# ads1299.net
KiCad netlist of a schematic drawn in Altium Designer
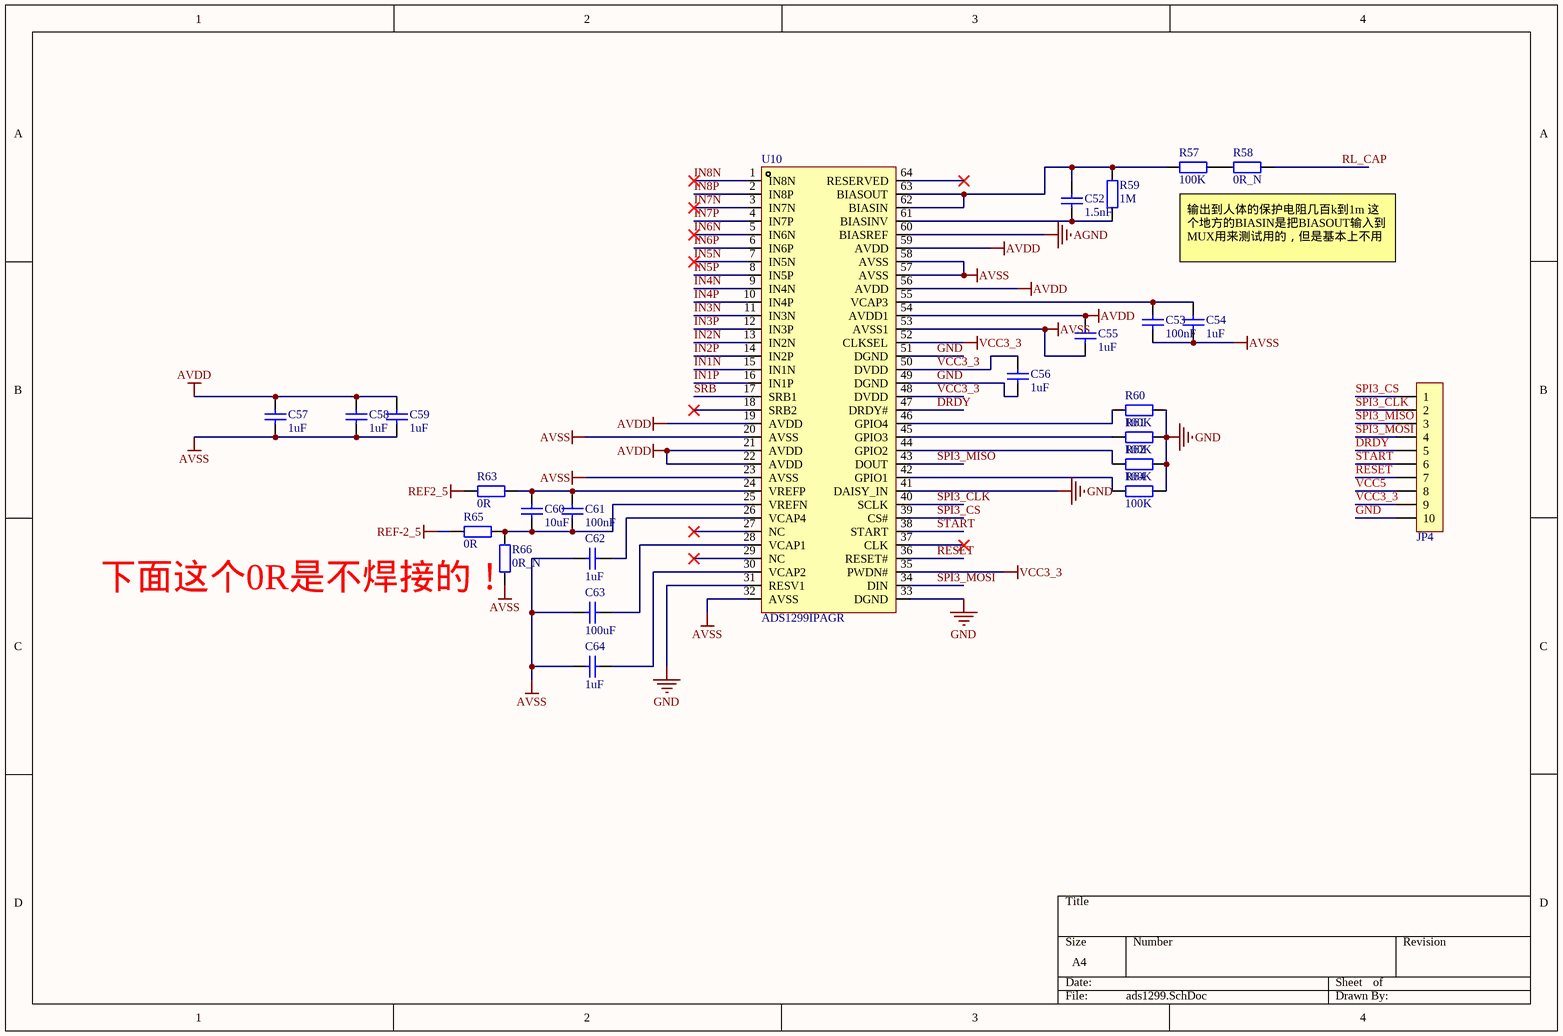
[diagram p0: ads1299.SchDoc]

(export (version "E")
  (design (tool "Eeschema 10.0.6"))
  (components
    (comp (ref "C52")
      (value "1.5nF")
      (footprint "C0603_L")
      (description "贴片电容/MLCC电容")
      (libsource (lib "0.1 - 电阻-电容-电感-保险丝-晶振-晶体-磁珠-电位器-法拉电容-馈通电容") (part "C"))
    )
    (comp (ref "C53")
      (value "100nF")
      (footprint "C0603_L")
      (description "贴片电容/MLCC电容")
      (libsource (lib "0.1 - 电阻-电容-电感-保险丝-晶振-晶体-磁珠-电位器-法拉电容-馈通电容") (part "C"))
    )
    (comp (ref "C54")
      (value "1uF")
      (footprint "C0603_L")
      (description "贴片电容/MLCC电容")
      (libsource (lib "0.1 - 电阻-电容-电感-保险丝-晶振-晶体-磁珠-电位器-法拉电容-馈通电容") (part "C"))
    )
    (comp (ref "C55")
      (value "1uF")
      (footprint "C0603_L")
      (description "贴片电容/MLCC电容")
      (libsource (lib "0.1 - 电阻-电容-电感-保险丝-晶振-晶体-磁珠-电位器-法拉电容-馈通电容") (part "C"))
    )
    (comp (ref "C56")
      (value "1uF")
      (footprint "C0603_L")
      (description "贴片电容/MLCC电容")
      (libsource (lib "0.1 - 电阻-电容-电感-保险丝-晶振-晶体-磁珠-电位器-法拉电容-馈通电容") (part "C"))
    )
    (comp (ref "C57")
      (value "1uF")
      (footprint "C0603_L")
      (description "贴片电容/MLCC电容")
      (libsource (lib "0.1 - 电阻-电容-电感-保险丝-晶振-晶体-磁珠-电位器-法拉电容-馈通电容") (part "C"))
    )
    (comp (ref "C58")
      (value "1uF")
      (footprint "C0603_L")
      (description "贴片电容/MLCC电容")
      (libsource (lib "0.1 - 电阻-电容-电感-保险丝-晶振-晶体-磁珠-电位器-法拉电容-馈通电容") (part "C"))
    )
    (comp (ref "C59")
      (value "1uF")
      (footprint "C0603_L")
      (description "贴片电容/MLCC电容")
      (libsource (lib "0.1 - 电阻-电容-电感-保险丝-晶振-晶体-磁珠-电位器-法拉电容-馈通电容") (part "C"))
    )
    (comp (ref "C60")
      (value "10uF")
      (footprint "C0603_L")
      (description "贴片电容/MLCC电容")
      (libsource (lib "0.1 - 电阻-电容-电感-保险丝-晶振-晶体-磁珠-电位器-法拉电容-馈通电容") (part "C"))
    )
    (comp (ref "C61")
      (value "100nF")
      (footprint "C0603_L")
      (description "贴片电容/MLCC电容")
      (libsource (lib "0.1 - 电阻-电容-电感-保险丝-晶振-晶体-磁珠-电位器-法拉电容-馈通电容") (part "C"))
    )
    (comp (ref "C62")
      (value "1uF")
      (footprint "C0603_L")
      (description "贴片电容/MLCC电容")
      (libsource (lib "0.1 - 电阻-电容-电感-保险丝-晶振-晶体-磁珠-电位器-法拉电容-馈通电容") (part "C"))
    )
    (comp (ref "C63")
      (value "100uF")
      (footprint "C1206_L")
      (description "贴片电容/MLCC电容")
      (libsource (lib "0.1 - 电阻-电容-电感-保险丝-晶振-晶体-磁珠-电位器-法拉电容-馈通电容") (part "C"))
    )
    (comp (ref "C64")
      (value "1uF")
      (footprint "C0603_L")
      (description "贴片电容/MLCC电容")
      (libsource (lib "0.1 - 电阻-电容-电感-保险丝-晶振-晶体-磁珠-电位器-法拉电容-馈通电容") (part "C"))
    )
    (comp (ref "JP4")
      (value "HDR-1X10")
      (footprint "HDR2.54-LI-10P")
      (description "10P接插件")
      (libsource (lib "5.5 - 2.54mm连接器(KF2EDGK_XH2.54_2.54排针排母)") (part "Header 10"))
    )
    (comp (ref "R57")
      (value "100K")
      (footprint "R0603_L")
      (description "贴片电阻")
      (libsource (lib "0.1 - 电阻-电容-电感-保险丝-晶振-晶体-磁珠-电位器-法拉电容-馈通电容") (part "R"))
    )
    (comp (ref "R58")
      (value "0R_N")
      (footprint "R0603_L")
      (description "贴片电阻")
      (libsource (lib "0.1 - 电阻-电容-电感-保险丝-晶振-晶体-磁珠-电位器-法拉电容-馈通电容") (part "R"))
    )
    (comp (ref "R59")
      (value "1M")
      (footprint "R0603_L")
      (description "贴片电阻")
      (libsource (lib "0.1 - 电阻-电容-电感-保险丝-晶振-晶体-磁珠-电位器-法拉电容-馈通电容") (part "R"))
    )
    (comp (ref "R60")
      (value "100K")
      (footprint "R0603_L")
      (description "贴片电阻")
      (libsource (lib "0.1 - 电阻-电容-电感-保险丝-晶振-晶体-磁珠-电位器-法拉电容-馈通电容") (part "R"))
    )
    (comp (ref "R61")
      (value "100K")
      (footprint "R0603_L")
      (description "贴片电阻")
      (libsource (lib "0.1 - 电阻-电容-电感-保险丝-晶振-晶体-磁珠-电位器-法拉电容-馈通电容") (part "R"))
    )
    (comp (ref "R62")
      (value "100K")
      (footprint "R0603_L")
      (description "贴片电阻")
      (libsource (lib "0.1 - 电阻-电容-电感-保险丝-晶振-晶体-磁珠-电位器-法拉电容-馈通电容") (part "R"))
    )
    (comp (ref "R63")
      (value "0R")
      (footprint "R0603_L")
      (description "贴片电阻")
      (libsource (lib "0.1 - 电阻-电容-电感-保险丝-晶振-晶体-磁珠-电位器-法拉电容-馈通电容") (part "R"))
    )
    (comp (ref "R64")
      (value "100K")
      (footprint "R0603_L")
      (description "贴片电阻")
      (libsource (lib "0.1 - 电阻-电容-电感-保险丝-晶振-晶体-磁珠-电位器-法拉电容-馈通电容") (part "R"))
    )
    (comp (ref "R65")
      (value "0R")
      (footprint "R0603_L")
      (description "贴片电阻")
      (libsource (lib "0.1 - 电阻-电容-电感-保险丝-晶振-晶体-磁珠-电位器-法拉电容-馈通电容") (part "R"))
    )
    (comp (ref "R66")
      (value "0R_N")
      (footprint "R0603_L")
      (description "贴片电阻")
      (libsource (lib "0.1 - 电阻-电容-电感-保险丝-晶振-晶体-磁珠-电位器-法拉电容-馈通电容") (part "R"))
    )
    (comp (ref "U10")
      (value "ADS1299IPAGR")
      (footprint "TQFP64_N")
      (description "24位、多通道EEG/ECG ADC，内置增益放大")
      (fields (field (name "MANUFACTURER") "TI(德州仪器)"))
      (libsource (lib "HT") (part "ADS1299IPAGR"))
    )
  )
  (nets
    (net (code "1") (name "/DRDY") (class "Default")
      (node (ref "JP4") (pin "5") (pinfunction "5_5") (pintype "passive"))
      (node (ref "U10") (pin "47") (pinfunction "DRDY#_47") (pintype "passive"))
    )
    (net (code "2") (name "/IN1N") (class "Default")
      (node (ref "U10") (pin "15") (pinfunction "IN1N_15") (pintype "passive"))
    )
    (net (code "3") (name "/IN1P") (class "Default")
      (node (ref "U10") (pin "16") (pinfunction "IN1P_16") (pintype "passive"))
    )
    (net (code "4") (name "/IN2N") (class "Default")
      (node (ref "U10") (pin "13") (pinfunction "IN2N_13") (pintype "passive"))
    )
    (net (code "5") (name "/IN2P") (class "Default")
      (node (ref "U10") (pin "14") (pinfunction "IN2P_14") (pintype "passive"))
    )
    (net (code "6") (name "/IN3N") (class "Default")
      (node (ref "U10") (pin "11") (pinfunction "IN3N_11") (pintype "passive"))
    )
    (net (code "7") (name "/IN3P") (class "Default")
      (node (ref "U10") (pin "12") (pinfunction "IN3P_12") (pintype "passive"))
    )
    (net (code "8") (name "/IN4N") (class "Default")
      (node (ref "U10") (pin "9") (pinfunction "IN4N_9") (pintype "passive"))
    )
    (net (code "9") (name "/IN4P") (class "Default")
      (node (ref "U10") (pin "10") (pinfunction "IN4P_10") (pintype "passive"))
    )
    (net (code "10") (name "/IN5N") (class "Default")
      (node (ref "U10") (pin "7") (pinfunction "IN5N_7") (pintype "passive+no_connect"))
    )
    (net (code "11") (name "/IN5P") (class "Default")
      (node (ref "U10") (pin "8") (pinfunction "IN5P_8") (pintype "passive"))
    )
    (net (code "12") (name "/IN6N") (class "Default")
      (node (ref "U10") (pin "5") (pinfunction "IN6N_5") (pintype "passive+no_connect"))
    )
    (net (code "13") (name "/IN6P") (class "Default")
      (node (ref "U10") (pin "6") (pinfunction "IN6P_6") (pintype "passive"))
    )
    (net (code "14") (name "/IN7N") (class "Default")
      (node (ref "U10") (pin "3") (pinfunction "IN7N_3") (pintype "passive+no_connect"))
    )
    (net (code "15") (name "/IN7P") (class "Default")
      (node (ref "U10") (pin "4") (pinfunction "IN7P_4") (pintype "passive"))
    )
    (net (code "16") (name "/IN8N") (class "Default")
      (node (ref "U10") (pin "1") (pinfunction "IN8N_1") (pintype "passive+no_connect"))
    )
    (net (code "17") (name "/IN8P") (class "Default")
      (node (ref "U10") (pin "2") (pinfunction "IN8P_2") (pintype "passive"))
    )
    (net (code "18") (name "/RESET") (class "Default")
      (node (ref "JP4") (pin "7") (pinfunction "7_7") (pintype "passive"))
      (node (ref "U10") (pin "36") (pinfunction "RESET#_36") (pintype "passive"))
    )
    (net (code "19") (name "/RL_CAP") (class "Default")
      (node (ref "R58") (pin "1") (pinfunction "1_1") (pintype "passive"))
    )
    (net (code "20") (name "/SPI3_CLK") (class "Default")
      (node (ref "JP4") (pin "2") (pinfunction "2_2") (pintype "passive"))
      (node (ref "U10") (pin "40") (pinfunction "SCLK_40") (pintype "passive"))
    )
    (net (code "21") (name "/SPI3_CS") (class "Default")
      (node (ref "JP4") (pin "1") (pinfunction "1_1") (pintype "passive"))
      (node (ref "U10") (pin "39") (pinfunction "CS#_39") (pintype "passive"))
    )
    (net (code "22") (name "/SPI3_MISO") (class "Default")
      (node (ref "JP4") (pin "3") (pinfunction "3_3") (pintype "passive"))
      (node (ref "U10") (pin "43") (pinfunction "DOUT_43") (pintype "passive"))
    )
    (net (code "23") (name "/SPI3_MOSI") (class "Default")
      (node (ref "JP4") (pin "4") (pinfunction "4_4") (pintype "passive"))
      (node (ref "U10") (pin "34") (pinfunction "DIN_34") (pintype "passive"))
    )
    (net (code "24") (name "/SRB") (class "Default")
      (node (ref "U10") (pin "17") (pinfunction "SRB1_17") (pintype "passive"))
    )
    (net (code "25") (name "/START") (class "Default")
      (node (ref "JP4") (pin "6") (pinfunction "6_6") (pintype "passive"))
      (node (ref "U10") (pin "38") (pinfunction "START_38") (pintype "passive"))
    )
    (net (code "26") (name "/VCC5") (class "Default")
      (node (ref "JP4") (pin "8") (pinfunction "8_8") (pintype "passive"))
    )
    (net (code "27") (name "AGND") (class "Default")
      (node (ref "U10") (pin "60") (pinfunction "BIASREF_60") (pintype "passive"))
    )
    (net (code "28") (name "AVDD") (class "Default")
      (node (ref "C55") (pin "2") (pinfunction "2_2") (pintype "passive"))
      (node (ref "C57") (pin "2") (pinfunction "2_2") (pintype "passive"))
      (node (ref "C58") (pin "2") (pinfunction "2_2") (pintype "passive"))
      (node (ref "C59") (pin "2") (pinfunction "2_2") (pintype "passive"))
      (node (ref "U10") (pin "19") (pinfunction "AVDD_19") (pintype "passive"))
      (node (ref "U10") (pin "21") (pinfunction "AVDD_21") (pintype "passive"))
      (node (ref "U10") (pin "22") (pinfunction "AVDD_22") (pintype "passive"))
      (node (ref "U10") (pin "54") (pinfunction "AVDD1_54") (pintype "passive"))
      (node (ref "U10") (pin "56") (pinfunction "AVDD_56") (pintype "passive"))
      (node (ref "U10") (pin "59") (pinfunction "AVDD_59") (pintype "passive"))
    )
    (net (code "29") (name "AVSS") (class "Default")
      (node (ref "C53") (pin "1") (pinfunction "1_1") (pintype "passive"))
      (node (ref "C54") (pin "1") (pinfunction "1_1") (pintype "passive"))
      (node (ref "C55") (pin "1") (pinfunction "1_1") (pintype "passive"))
      (node (ref "C57") (pin "1") (pinfunction "1_1") (pintype "passive"))
      (node (ref "C58") (pin "1") (pinfunction "1_1") (pintype "passive"))
      (node (ref "C59") (pin "1") (pinfunction "1_1") (pintype "passive"))
      (node (ref "C62") (pin "1") (pinfunction "1_1") (pintype "passive"))
      (node (ref "C63") (pin "2") (pinfunction "2_2") (pintype "passive"))
      (node (ref "C64") (pin "1") (pinfunction "1_1") (pintype "passive"))
      (node (ref "R66") (pin "2") (pinfunction "2_2") (pintype "passive"))
      (node (ref "U10") (pin "20") (pinfunction "AVSS_20") (pintype "passive"))
      (node (ref "U10") (pin "23") (pinfunction "AVSS_23") (pintype "passive"))
      (node (ref "U10") (pin "32") (pinfunction "AVSS_32") (pintype "passive"))
      (node (ref "U10") (pin "53") (pinfunction "AVSS1_53") (pintype "passive"))
      (node (ref "U10") (pin "57") (pinfunction "AVSS_57") (pintype "passive"))
      (node (ref "U10") (pin "58") (pinfunction "AVSS_58") (pintype "passive"))
    )
    (net (code "30") (name "GND") (class "Default")
      (node (ref "C56") (pin "1") (pinfunction "1_1") (pintype "passive"))
      (node (ref "JP4") (pin "10") (pinfunction "10_10") (pintype "passive"))
      (node (ref "R60") (pin "2") (pinfunction "2_2") (pintype "passive"))
      (node (ref "R61") (pin "2") (pinfunction "2_2") (pintype "passive"))
      (node (ref "R62") (pin "2") (pinfunction "2_2") (pintype "passive"))
      (node (ref "R64") (pin "2") (pinfunction "2_2") (pintype "passive"))
      (node (ref "U10") (pin "31") (pinfunction "RESV1_31") (pintype "passive"))
      (node (ref "U10") (pin "33") (pinfunction "DGND_33") (pintype "passive"))
      (node (ref "U10") (pin "41") (pinfunction "DAISY_IN_41") (pintype "passive"))
      (node (ref "U10") (pin "49") (pinfunction "DGND_49") (pintype "passive"))
      (node (ref "U10") (pin "51") (pinfunction "DGND_51") (pintype "passive"))
    )
    (net (code "31") (name "Net-(R57-Pad2)") (class "Default")
      (node (ref "R57") (pin "2") (pinfunction "2_2") (pintype "passive"))
      (node (ref "R58") (pin "2") (pinfunction "2_2") (pintype "passive"))
    )
    (net (code "32") (name "Net-(U10-BIASIN)") (class "Default")
      (node (ref "C52") (pin "2") (pinfunction "2_2") (pintype "passive"))
      (node (ref "R57") (pin "1") (pinfunction "1_1") (pintype "passive"))
      (node (ref "R59") (pin "1") (pinfunction "1_1") (pintype "passive"))
      (node (ref "U10") (pin "62") (pinfunction "BIASIN_62") (pintype "passive"))
      (node (ref "U10") (pin "63") (pinfunction "BIASOUT_63") (pintype "passive"))
    )
    (net (code "33") (name "Net-(U10-BIASINV)") (class "Default")
      (node (ref "C52") (pin "1") (pinfunction "1_1") (pintype "passive"))
      (node (ref "R59") (pin "2") (pinfunction "2_2") (pintype "passive"))
      (node (ref "U10") (pin "61") (pinfunction "BIASINV_61") (pintype "passive"))
    )
    (net (code "34") (name "Net-(U10-GPIO1)") (class "Default")
      (node (ref "R64") (pin "1") (pinfunction "1_1") (pintype "passive"))
      (node (ref "U10") (pin "42") (pinfunction "GPIO1_42") (pintype "passive"))
    )
    (net (code "35") (name "Net-(U10-GPIO2)") (class "Default")
      (node (ref "R62") (pin "1") (pinfunction "1_1") (pintype "passive"))
      (node (ref "U10") (pin "44") (pinfunction "GPIO2_44") (pintype "passive"))
    )
    (net (code "36") (name "Net-(U10-GPIO3)") (class "Default")
      (node (ref "R61") (pin "1") (pinfunction "1_1") (pintype "passive"))
      (node (ref "U10") (pin "45") (pinfunction "GPIO3_45") (pintype "passive"))
    )
    (net (code "37") (name "Net-(U10-GPIO4)") (class "Default")
      (node (ref "R60") (pin "1") (pinfunction "1_1") (pintype "passive"))
      (node (ref "U10") (pin "46") (pinfunction "GPIO4_46") (pintype "passive"))
    )
    (net (code "38") (name "Net-(U10-VCAP1)") (class "Default")
      (node (ref "C63") (pin "1") (pinfunction "1_1") (pintype "passive"))
      (node (ref "U10") (pin "28") (pinfunction "VCAP1_28") (pintype "passive"))
    )
    (net (code "39") (name "Net-(U10-VCAP2)") (class "Default")
      (node (ref "C64") (pin "2") (pinfunction "2_2") (pintype "passive"))
      (node (ref "U10") (pin "30") (pinfunction "VCAP2_30") (pintype "passive"))
    )
    (net (code "40") (name "Net-(U10-VCAP3)") (class "Default")
      (node (ref "C53") (pin "2") (pinfunction "2_2") (pintype "passive"))
      (node (ref "C54") (pin "2") (pinfunction "2_2") (pintype "passive"))
      (node (ref "U10") (pin "55") (pinfunction "VCAP3_55") (pintype "passive"))
    )
    (net (code "41") (name "Net-(U10-VCAP4)") (class "Default")
      (node (ref "C62") (pin "2") (pinfunction "2_2") (pintype "passive"))
      (node (ref "U10") (pin "26") (pinfunction "VCAP4_26") (pintype "passive"))
    )
    (net (code "42") (name "Net-(U10-VREFN)") (class "Default")
      (node (ref "C60") (pin "1") (pinfunction "1_1") (pintype "passive"))
      (node (ref "C61") (pin "1") (pinfunction "1_1") (pintype "passive"))
      (node (ref "R65") (pin "1") (pinfunction "1_1") (pintype "passive"))
      (node (ref "R66") (pin "1") (pinfunction "1_1") (pintype "passive"))
      (node (ref "U10") (pin "25") (pinfunction "VREFN_25") (pintype "passive"))
    )
    (net (code "43") (name "Net-(U10-VREFP)") (class "Default")
      (node (ref "C60") (pin "2") (pinfunction "2_2") (pintype "passive"))
      (node (ref "C61") (pin "2") (pinfunction "2_2") (pintype "passive"))
      (node (ref "R63") (pin "1") (pinfunction "1_1") (pintype "passive"))
      (node (ref "U10") (pin "24") (pinfunction "VREFP_24") (pintype "passive"))
    )
    (net (code "44") (name "REF-2_5") (class "Default")
      (node (ref "R65") (pin "2") (pinfunction "2_2") (pintype "passive"))
    )
    (net (code "45") (name "REF2_5") (class "Default")
      (node (ref "R63") (pin "2") (pinfunction "2_2") (pintype "passive"))
    )
    (net (code "46") (name "VCC3_3") (class "Default")
      (node (ref "C56") (pin "2") (pinfunction "2_2") (pintype "passive"))
      (node (ref "JP4") (pin "9") (pinfunction "9_9") (pintype "passive"))
      (node (ref "U10") (pin "35") (pinfunction "PWDN#_35") (pintype "passive"))
      (node (ref "U10") (pin "48") (pinfunction "DVDD_48") (pintype "passive"))
      (node (ref "U10") (pin "50") (pinfunction "DVDD_50") (pintype "passive"))
      (node (ref "U10") (pin "52") (pinfunction "CLKSEL_52") (pintype "passive"))
    )
    (net (code "47") (name "unconnected-(U10-CLK-Pad37)") (class "Default")
      (node (ref "U10") (pin "37") (pinfunction "CLK_37") (pintype "passive+no_connect"))
    )
    (net (code "48") (name "unconnected-(U10-NC-Pad27)") (class "Default")
      (node (ref "U10") (pin "27") (pinfunction "NC_27") (pintype "passive+no_connect"))
    )
    (net (code "49") (name "unconnected-(U10-NC-Pad29)") (class "Default")
      (node (ref "U10") (pin "29") (pinfunction "NC_29") (pintype "passive+no_connect"))
    )
    (net (code "50") (name "unconnected-(U10-RESERVED-Pad64)") (class "Default")
      (node (ref "U10") (pin "64") (pinfunction "RESERVED_64") (pintype "passive+no_connect"))
    )
    (net (code "51") (name "unconnected-(U10-SRB2-Pad18)") (class "Default")
      (node (ref "U10") (pin "18") (pinfunction "SRB2_18") (pintype "passive+no_connect"))
    )
  )
)
